# Woolllf_Open_Weeve_CE.net
KiCad netlist of a schematic drawn in EAGLE
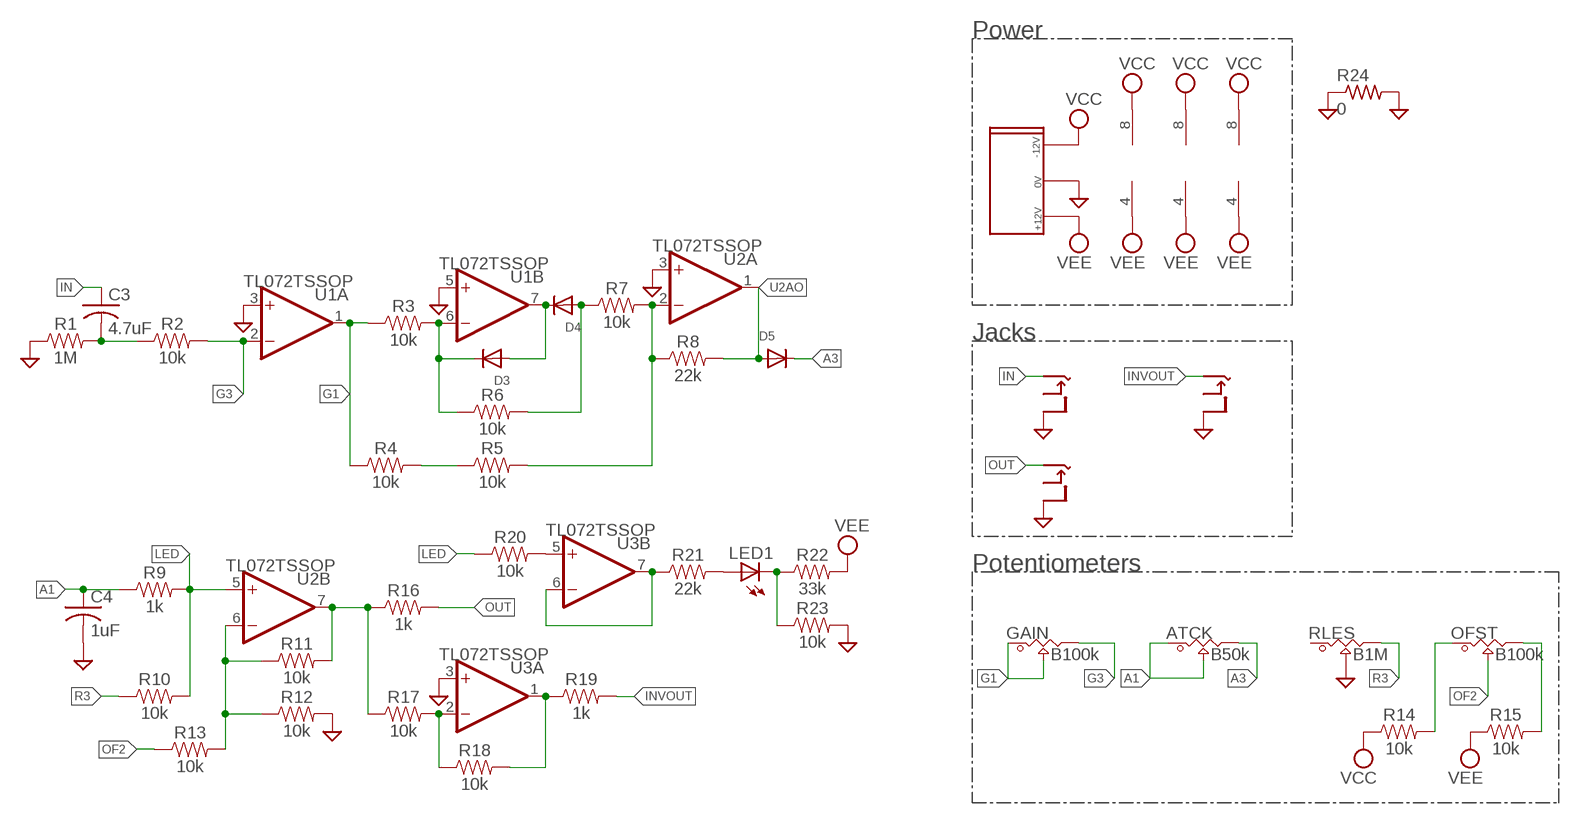
[diagram p0: schematic, sheet 1]

(export (version "E")
  (design (tool "Eeschema 10.0.6"))
  (components
    (comp (ref "ATCK")
      (value "B50k")
      (footprint "eagle-import:POT_9MM_SMD")
      (libsource (lib "eagle-import") (part "POT_9MM_SMD"))
    )
    (comp (ref "C3")
      (value "4.7uF")
      (footprint "eagle-import:C0603")
      (libsource (lib "eagle-import") (part "C-USC0603"))
    )
    (comp (ref "C4")
      (value "1uF")
      (footprint "eagle-import:C0603")
      (libsource (lib "eagle-import") (part "C-USC0603"))
    )
    (comp (ref "D3")
      (value "DIODESOD-123")
      (footprint "eagle-import:SOD-123")
      (libsource (lib "eagle-import") (part "DIODESOD-123"))
    )
    (comp (ref "D4")
      (value "DIODESOD-123")
      (footprint "eagle-import:SOD-123")
      (libsource (lib "eagle-import") (part "DIODESOD-123"))
    )
    (comp (ref "D5")
      (value "DIODESOD-123")
      (footprint "eagle-import:SOD-123")
      (libsource (lib "eagle-import") (part "DIODESOD-123"))
    )
    (comp (ref "GAIN")
      (value "B100k")
      (footprint "eagle-import:POT_9MM_SMD")
      (libsource (lib "eagle-import") (part "POT_9MM_SMD"))
    )
    (comp (ref "LED1")
      (value "LEDCHIP-LED0603")
      (footprint "eagle-import:CHIP-LED0603")
      (libsource (lib "eagle-import") (part "LEDCHIP-LED0603"))
    )
    (comp (ref "OFST")
      (value "B100k")
      (footprint "eagle-import:POT_9MM_SMD")
      (libsource (lib "eagle-import") (part "POT_9MM_SMD"))
    )
    (comp (ref "R1")
      (value "1M")
      (footprint "eagle-import:0603")
      (libsource (lib "eagle-import") (part "RESISTOR0603"))
    )
    (comp (ref "R2")
      (value "10k")
      (footprint "eagle-import:0603")
      (libsource (lib "eagle-import") (part "RESISTOR0603"))
    )
    (comp (ref "R3")
      (value "10k")
      (footprint "eagle-import:0603")
      (libsource (lib "eagle-import") (part "RESISTOR0603"))
    )
    (comp (ref "R4")
      (value "10k")
      (footprint "eagle-import:0603")
      (libsource (lib "eagle-import") (part "RESISTOR0603"))
    )
    (comp (ref "R5")
      (value "10k")
      (footprint "eagle-import:0603")
      (libsource (lib "eagle-import") (part "RESISTOR0603"))
    )
    (comp (ref "R6")
      (value "10k")
      (footprint "eagle-import:0603")
      (libsource (lib "eagle-import") (part "RESISTOR0603"))
    )
    (comp (ref "R7")
      (value "10k")
      (footprint "eagle-import:0603")
      (libsource (lib "eagle-import") (part "RESISTOR0603"))
    )
    (comp (ref "R8")
      (value "22k")
      (footprint "eagle-import:0603")
      (libsource (lib "eagle-import") (part "RESISTOR0603"))
    )
    (comp (ref "R9")
      (value "1k")
      (footprint "eagle-import:0603")
      (libsource (lib "eagle-import") (part "RESISTOR0603"))
    )
    (comp (ref "R10")
      (value "10k")
      (footprint "eagle-import:0603")
      (libsource (lib "eagle-import") (part "RESISTOR0603"))
    )
    (comp (ref "R11")
      (value "10k")
      (footprint "eagle-import:0603")
      (libsource (lib "eagle-import") (part "RESISTOR0603"))
    )
    (comp (ref "R12")
      (value "10k")
      (footprint "eagle-import:0603")
      (libsource (lib "eagle-import") (part "RESISTOR0603"))
    )
    (comp (ref "R13")
      (value "10k")
      (footprint "eagle-import:0603")
      (libsource (lib "eagle-import") (part "RESISTOR0603"))
    )
    (comp (ref "R14")
      (value "10k")
      (footprint "eagle-import:0603")
      (libsource (lib "eagle-import") (part "RESISTOR0603"))
    )
    (comp (ref "R15")
      (value "10k")
      (footprint "eagle-import:0603")
      (libsource (lib "eagle-import") (part "RESISTOR0603"))
    )
    (comp (ref "R16")
      (value "1k")
      (footprint "eagle-import:0603")
      (libsource (lib "eagle-import") (part "RESISTOR0603"))
    )
    (comp (ref "R17")
      (value "10k")
      (footprint "eagle-import:0603")
      (libsource (lib "eagle-import") (part "RESISTOR0603"))
    )
    (comp (ref "R18")
      (value "10k")
      (footprint "eagle-import:0603")
      (libsource (lib "eagle-import") (part "RESISTOR0603"))
    )
    (comp (ref "R19")
      (value "1k")
      (footprint "eagle-import:0603")
      (libsource (lib "eagle-import") (part "RESISTOR0603"))
    )
    (comp (ref "R20")
      (value "10k")
      (footprint "eagle-import:0603")
      (libsource (lib "eagle-import") (part "RESISTOR0603"))
    )
    (comp (ref "R21")
      (value "22k")
      (footprint "eagle-import:0603")
      (libsource (lib "eagle-import") (part "RESISTOR0603"))
    )
    (comp (ref "R22")
      (value "33k")
      (footprint "eagle-import:0603")
      (libsource (lib "eagle-import") (part "RESISTOR0603"))
    )
    (comp (ref "R23")
      (value "10k")
      (footprint "eagle-import:0603")
      (libsource (lib "eagle-import") (part "RESISTOR0603"))
    )
    (comp (ref "R24")
      (value "0")
      (footprint "eagle-import:R0402")
      (libsource (lib "eagle-import") (part "R-US_R0402"))
    )
    (comp (ref "RLES")
      (value "B1M")
      (footprint "eagle-import:POT_9MM_SMD")
      (libsource (lib "eagle-import") (part "POT_9MM_SMD"))
    )
    (comp (ref "U$1")
      (value "EURO_POW_CEH")
      (footprint "eagle-import:EURO_POW_CEH")
      (libsource (lib "eagle-import") (part "EURO_POW_CEH"))
    )
    (comp (ref "U$2")
      (value "THONKICONN_CE_3X_COMG_NOSW")
      (footprint "eagle-import:1.27MM_CE_3X_COMG_NOSW")
      (libsource (lib "eagle-import") (part "THONKICONN_CE_3X_COMG_NOSW"))
    )
    (comp (ref "U1")
      (value "TL072TSSOP")
      (footprint "eagle-import:TSSOP-8")
      (libsource (lib "eagle-import") (part "TL072TSSOP"))
    )
    (comp (ref "U2")
      (value "TL072TSSOP")
      (footprint "eagle-import:TSSOP-8")
      (libsource (lib "eagle-import") (part "TL072TSSOP"))
    )
    (comp (ref "U3")
      (value "TL072TSSOP")
      (footprint "eagle-import:TSSOP-8")
      (libsource (lib "eagle-import") (part "TL072TSSOP"))
    )
  )
  (nets
    (net (code "1") (name "A1") (class "Default")
      (node (ref "ATCK") (pin "1") (pinfunction "1_1") (pintype "bidirectional"))
      (node (ref "ATCK") (pin "2") (pinfunction "2_2") (pintype "bidirectional"))
      (node (ref "C4") (pin "1") (pinfunction "1_1") (pintype "passive"))
      (node (ref "R9") (pin "1") (pinfunction "1_1") (pintype "passive"))
    )
    (net (code "2") (name "A3") (class "Default")
      (node (ref "ATCK") (pin "3") (pinfunction "3_3") (pintype "bidirectional"))
      (node (ref "D5") (pin "C") (pinfunction "C_C") (pintype "passive"))
    )
    (net (code "3") (name "G1") (class "Default")
      (node (ref "GAIN") (pin "1") (pinfunction "1_1") (pintype "bidirectional"))
      (node (ref "GAIN") (pin "2") (pinfunction "2_2") (pintype "bidirectional"))
      (node (ref "R3") (pin "1") (pinfunction "1_1") (pintype "passive"))
      (node (ref "R4") (pin "1") (pinfunction "1_1") (pintype "passive"))
      (node (ref "U1") (pin "1") (pinfunction "OUT_1") (pintype "output"))
    )
    (net (code "4") (name "G3") (class "Default")
      (node (ref "GAIN") (pin "3") (pinfunction "3_3") (pintype "bidirectional"))
      (node (ref "R2") (pin "2") (pinfunction "2_2") (pintype "passive"))
      (node (ref "U1") (pin "2") (pinfunction "-IN_2") (pintype "input"))
    )
    (net (code "5") (name "GND") (class "Default")
      (node (ref "C4") (pin "2") (pinfunction "2_2") (pintype "passive"))
      (node (ref "R1") (pin "1") (pinfunction "1_1") (pintype "passive"))
      (node (ref "R12") (pin "2") (pinfunction "2_2") (pintype "passive"))
      (node (ref "R23") (pin "2") (pinfunction "2_2") (pintype "passive"))
      (node (ref "R24") (pin "1") (pinfunction "1_1") (pintype "passive"))
      (node (ref "R24") (pin "2") (pinfunction "2_2") (pintype "passive"))
      (node (ref "RLES") (pin "2") (pinfunction "2_2") (pintype "bidirectional"))
      (node (ref "U$1") (pin "GND") (pinfunction "GND_GND") (pintype "bidirectional"))
      (node (ref "U$2") (pin "0") (pinfunction "S_0") (pintype "bidirectional"))
      (node (ref "U1") (pin "3") (pinfunction "+IN_3") (pintype "input"))
      (node (ref "U1") (pin "5") (pinfunction "+IN_5") (pintype "input"))
      (node (ref "U2") (pin "3") (pinfunction "+IN_3") (pintype "input"))
      (node (ref "U3") (pin "3") (pinfunction "+IN_3") (pintype "input"))
    )
    (net (code "6") (name "IN") (class "Default")
      (node (ref "C3") (pin "1") (pinfunction "1_1") (pintype "passive"))
      (node (ref "U$2") (pin "1") (pinfunction "T_1") (pintype "bidirectional"))
    )
    (net (code "7") (name "INVOUT") (class "Default")
      (node (ref "R19") (pin "2") (pinfunction "2_2") (pintype "passive"))
      (node (ref "U$2") (pin "2") (pinfunction "T_2") (pintype "bidirectional"))
    )
    (net (code "8") (name "LED") (class "Default")
      (node (ref "R10") (pin "2") (pinfunction "2_2") (pintype "passive"))
      (node (ref "R20") (pin "1") (pinfunction "1_1") (pintype "passive"))
      (node (ref "R9") (pin "2") (pinfunction "2_2") (pintype "passive"))
      (node (ref "U2") (pin "5") (pinfunction "+IN_5") (pintype "input"))
    )
    (net (code "9") (name "Net-(C3-Pad2)") (class "Default")
      (node (ref "C3") (pin "2") (pinfunction "2_2") (pintype "passive"))
      (node (ref "R1") (pin "2") (pinfunction "2_2") (pintype "passive"))
      (node (ref "R2") (pin "1") (pinfunction "1_1") (pintype "passive"))
    )
    (net (code "10") (name "Net-(D4-PadA)") (class "Default")
      (node (ref "D4") (pin "A") (pinfunction "A_A") (pintype "passive"))
      (node (ref "R6") (pin "2") (pinfunction "2_2") (pintype "passive"))
      (node (ref "R7") (pin "1") (pinfunction "1_1") (pintype "passive"))
    )
    (net (code "11") (name "Net-(LED1-PadA)") (class "Default")
      (node (ref "LED1") (pin "A") (pinfunction "A_A") (pintype "passive"))
      (node (ref "R21") (pin "2") (pinfunction "2_2") (pintype "passive"))
    )
    (net (code "12") (name "Net-(LED1-PadC)") (class "Default")
      (node (ref "LED1") (pin "C") (pinfunction "C_C") (pintype "passive"))
      (node (ref "R22") (pin "1") (pinfunction "1_1") (pintype "passive"))
      (node (ref "R23") (pin "1") (pinfunction "1_1") (pintype "passive"))
    )
    (net (code "13") (name "Net-(OFST-Pad1)") (class "Default")
      (node (ref "OFST") (pin "1") (pinfunction "1_1") (pintype "bidirectional"))
      (node (ref "R14") (pin "2") (pinfunction "2_2") (pintype "passive"))
    )
    (net (code "14") (name "Net-(OFST-Pad3)") (class "Default")
      (node (ref "OFST") (pin "3") (pinfunction "3_3") (pintype "bidirectional"))
      (node (ref "R15") (pin "2") (pinfunction "2_2") (pintype "passive"))
    )
    (net (code "15") (name "Net-(R4-Pad2)") (class "Default")
      (node (ref "R4") (pin "2") (pinfunction "2_2") (pintype "passive"))
      (node (ref "R5") (pin "1") (pinfunction "1_1") (pintype "passive"))
    )
    (net (code "16") (name "Net-(U1B--IN)") (class "Default")
      (node (ref "D3") (pin "C") (pinfunction "C_C") (pintype "passive"))
      (node (ref "R3") (pin "2") (pinfunction "2_2") (pintype "passive"))
      (node (ref "R6") (pin "1") (pinfunction "1_1") (pintype "passive"))
      (node (ref "U1") (pin "6") (pinfunction "-IN_6") (pintype "input"))
    )
    (net (code "17") (name "Net-(U1B-OUT)") (class "Default")
      (node (ref "D3") (pin "A") (pinfunction "A_A") (pintype "passive"))
      (node (ref "D4") (pin "C") (pinfunction "C_C") (pintype "passive"))
      (node (ref "U1") (pin "7") (pinfunction "OUT_7") (pintype "output"))
    )
    (net (code "18") (name "Net-(U2A--IN)") (class "Default")
      (node (ref "R5") (pin "2") (pinfunction "2_2") (pintype "passive"))
      (node (ref "R7") (pin "2") (pinfunction "2_2") (pintype "passive"))
      (node (ref "R8") (pin "1") (pinfunction "1_1") (pintype "passive"))
      (node (ref "U2") (pin "2") (pinfunction "-IN_2") (pintype "input"))
    )
    (net (code "19") (name "Net-(U2B--IN)") (class "Default")
      (node (ref "R11") (pin "1") (pinfunction "1_1") (pintype "passive"))
      (node (ref "R12") (pin "1") (pinfunction "1_1") (pintype "passive"))
      (node (ref "R13") (pin "2") (pinfunction "2_2") (pintype "passive"))
      (node (ref "U2") (pin "6") (pinfunction "-IN_6") (pintype "input"))
    )
    (net (code "20") (name "Net-(U2B-OUT)") (class "Default")
      (node (ref "R11") (pin "2") (pinfunction "2_2") (pintype "passive"))
      (node (ref "R16") (pin "1") (pinfunction "1_1") (pintype "passive"))
      (node (ref "R17") (pin "1") (pinfunction "1_1") (pintype "passive"))
      (node (ref "U2") (pin "7") (pinfunction "OUT_7") (pintype "output"))
    )
    (net (code "21") (name "Net-(U3A--IN)") (class "Default")
      (node (ref "R17") (pin "2") (pinfunction "2_2") (pintype "passive"))
      (node (ref "R18") (pin "1") (pinfunction "1_1") (pintype "passive"))
      (node (ref "U3") (pin "2") (pinfunction "-IN_2") (pintype "input"))
    )
    (net (code "22") (name "Net-(U3A-OUT)") (class "Default")
      (node (ref "R18") (pin "2") (pinfunction "2_2") (pintype "passive"))
      (node (ref "R19") (pin "1") (pinfunction "1_1") (pintype "passive"))
      (node (ref "U3") (pin "1") (pinfunction "OUT_1") (pintype "output"))
    )
    (net (code "23") (name "Net-(U3B-+IN)") (class "Default")
      (node (ref "R20") (pin "2") (pinfunction "2_2") (pintype "passive"))
      (node (ref "U3") (pin "5") (pinfunction "+IN_5") (pintype "input"))
    )
    (net (code "24") (name "Net-(U3B--IN)") (class "Default")
      (node (ref "R21") (pin "1") (pinfunction "1_1") (pintype "passive"))
      (node (ref "U3") (pin "6") (pinfunction "-IN_6") (pintype "input"))
      (node (ref "U3") (pin "7") (pinfunction "OUT_7") (pintype "output"))
    )
    (net (code "25") (name "OF2") (class "Default")
      (node (ref "OFST") (pin "2") (pinfunction "2_2") (pintype "bidirectional"))
      (node (ref "R13") (pin "1") (pinfunction "1_1") (pintype "passive"))
    )
    (net (code "26") (name "OUT") (class "Default")
      (node (ref "R16") (pin "2") (pinfunction "2_2") (pintype "passive"))
      (node (ref "U$2") (pin "3") (pinfunction "T_3") (pintype "bidirectional"))
    )
    (net (code "27") (name "R3") (class "Default")
      (node (ref "R10") (pin "1") (pinfunction "1_1") (pintype "passive"))
      (node (ref "RLES") (pin "3") (pinfunction "3_3") (pintype "bidirectional"))
    )
    (net (code "28") (name "U2AO") (class "Default")
      (node (ref "D5") (pin "A") (pinfunction "A_A") (pintype "passive"))
      (node (ref "R8") (pin "2") (pinfunction "2_2") (pintype "passive"))
      (node (ref "U2") (pin "1") (pinfunction "OUT_1") (pintype "output"))
    )
    (net (code "29") (name "VCC") (class "Default")
      (node (ref "R14") (pin "1") (pinfunction "1_1") (pintype "passive"))
      (node (ref "U$1") (pin "-12V") (pinfunction "-12V_-12V") (pintype "bidirectional"))
      (node (ref "U1") (pin "8") (pinfunction "V+_8") (pintype "power_in"))
      (node (ref "U2") (pin "8") (pinfunction "V+_8") (pintype "power_in"))
      (node (ref "U3") (pin "8") (pinfunction "V+_8") (pintype "power_in"))
    )
    (net (code "30") (name "VEE") (class "Default")
      (node (ref "R15") (pin "1") (pinfunction "1_1") (pintype "passive"))
      (node (ref "R22") (pin "2") (pinfunction "2_2") (pintype "passive"))
      (node (ref "U$1") (pin "+12V") (pinfunction "+12V_+12V") (pintype "bidirectional"))
      (node (ref "U1") (pin "4") (pinfunction "V-_4") (pintype "power_in"))
      (node (ref "U2") (pin "4") (pinfunction "V-_4") (pintype "power_in"))
      (node (ref "U3") (pin "4") (pinfunction "V-_4") (pintype "power_in"))
    )
    (net (code "31") (name "unconnected-(RLES-Pad1)") (class "Default")
      (node (ref "RLES") (pin "1") (pinfunction "1_1") (pintype "bidirectional"))
    )
  )
)
